# HVstuff.net
KiCad netlist of a schematic drawn in Altium Designer
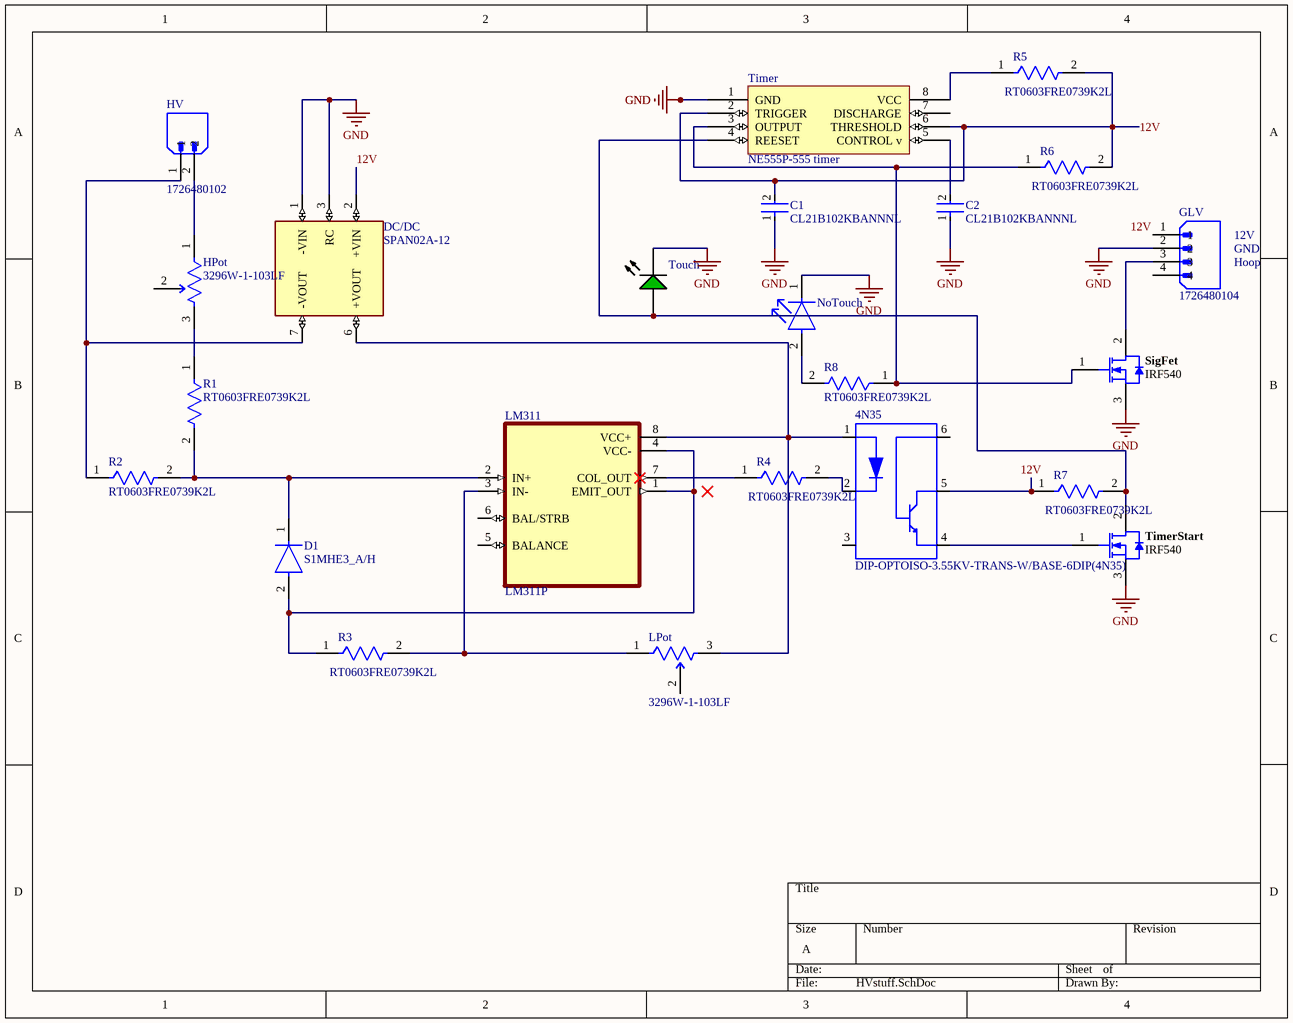
[diagram p0: HVstuff.SchDoc]

(export (version "E")
  (design (tool "Eeschema 10.0.6"))
  (components
    (comp (ref "4N35")
      (value "DIP-OPTOISO-3.55KV-TRANS-W/BASE-6DIP(4N35)")
      (footprint "DIP6-2.54-7.3X6.5MM")
      (description "Optoisolator Transistor with Base Output 5000Vrms 1 Channel 6-DIP")
      (fields (field (name "MF") "Vishay") (field (name "MP") "4N35"))
      (libsource (lib "DIP-OPTOISO-3.55KV-TRANS-W_BASE-6DIP_4N35_") (part "DIP-OPTOISO-3.55KV-TRANS-W/BASE-6DIP(4N35)"))
    )
    (comp (ref "C1")
      (value "CL21B102KBANNNL")
      (footprint "FP-CL21-IPC_A")
      (description "CL21 Series 0805 1nF 50V ±10% Tolerance X7R Multilayer Ceramic Chip Capacitor")
      (fields (field (name "TOLERANCE") "10%") (field (name "VOLTAGE") "50V"))
      (libsource (lib "Altium Content Vault") (part "b4654b650e69147ec39a6b967a45e02"))
    )
    (comp (ref "C2")
      (value "CL21B102KBANNNL")
      (footprint "FP-CL21-IPC_A")
      (description "CL21 Series 0805 1nF 50V ±10% Tolerance X7R Multilayer Ceramic Chip Capacitor")
      (fields (field (name "TOLERANCE") "10%") (field (name "VOLTAGE") "50V"))
      (libsource (lib "Altium Content Vault") (part "b4654b650e69147ec39a6b967a45e02"))
    )
    (comp (ref "D1")
      (value "S1MHE3_A/H")
      (footprint "FP-SMA-MFG")
      (description "DIODE GEN PURP 1KV 1A DO214AC")
      (libsource (lib "Altium Content Vault") (part "d7152d700b627762746794eb795d46e"))
    )
    (comp (ref "DC/DC")
      (value "SPAN02A-12")
      (footprint "SPAN02")
      (description "Isolated Module DC DC Converter 1 Output 12V - - - 167mA 9V - 18V Input")
      (fields (field (name "MF") "MEAN WELL USA Inc."))
      (libsource (lib "SPAN02A-12") (part "SPAN02A-12"))
    )
    (comp (ref "GLV")
      (value "1726480104")
      (footprint "MOLEX_1726480104")
      (description "Connector Header Through Hole, Right Angle 4 position 0.165in (4.20mm)")
      (libsource (lib "1726480104") (part "1726480104"))
    )
    (comp (ref "HPot")
      (value "3296W-1-103LF")
      (footprint "FP-3296W-MFG")
      (description "TRIMMER 10K OHM 0.5W PC PIN TOP")
      (fields (field (name "TOLERANCE") "10%"))
      (libsource (lib "Altium Content Vault") (part "2dcfd2547301a7d3209a5e99acfd772"))
    )
    (comp (ref "HV")
      (value "1726480102")
      (footprint "MOLEX_1726480102")
      (description "Connector Header Through Hole, Right Angle 2 position 0.165in (4.20mm)")
      (libsource (lib "1726480102") (part "1726480102"))
    )
    (comp (ref "LM311")
      (value "LM311P")
      (footprint "DIP794W45P254L959H508Q8")
      (description "High Speed, 30V, Differential Comparator With Strobes 8-PDIP 0 to 70")
      (fields (field (name "MF") "Texas Instruments"))
      (libsource (lib "LM311P") (part "LM311P"))
    )
    (comp (ref "LPot")
      (value "3296W-1-103LF")
      (footprint "FP-3296W-MFG")
      (description "TRIMMER 10K OHM 0.5W PC PIN TOP")
      (fields (field (name "TOLERANCE") "10%"))
      (libsource (lib "Altium Content Vault") (part "2dcfd2547301a7d3209a5e99acfd772"))
    )
    (comp (ref "NoTouch")
      (value "HSMS-C170")
      (footprint "FP-HSMS-C170-MFG")
      (description "LED RED DIFFUSED CHIP SMD")
      (libsource (lib "Altium Content Vault") (part "8706943c75ba83719d021d2fdc84c58"))
    )
    (comp (ref "R1")
      (value "RT0603FRE0739K2L")
      (footprint "FP-RT0603-MFG")
      (description "RES SMD 39.2K OHM 1% 1/10W 0603")
      (fields (field (name "MANUFACTURER") "Yageo") (field (name "TOLERANCE") "0.01"))
      (libsource (lib "Altium Content Vault") (part "1029c3af85768c4190bb7ad29bc67b5"))
    )
    (comp (ref "R2")
      (value "RT0603FRE0739K2L")
      (footprint "FP-RT0603-MFG")
      (description "RES SMD 39.2K OHM 1% 1/10W 0603")
      (fields (field (name "MANUFACTURER") "Yageo") (field (name "TOLERANCE") "0.01"))
      (libsource (lib "Altium Content Vault") (part "1029c3af85768c4190bb7ad29bc67b5"))
    )
    (comp (ref "R3")
      (value "RT0603FRE0739K2L")
      (footprint "FP-RT0603-MFG")
      (description "RES SMD 39.2K OHM 1% 1/10W 0603")
      (fields (field (name "MANUFACTURER") "Yageo") (field (name "TOLERANCE") "0.01"))
      (libsource (lib "Altium Content Vault") (part "1029c3af85768c4190bb7ad29bc67b5"))
    )
    (comp (ref "R4")
      (value "RT0603FRE0739K2L")
      (footprint "FP-RT0603-MFG")
      (description "RES SMD 39.2K OHM 1% 1/10W 0603")
      (fields (field (name "MANUFACTURER") "Yageo") (field (name "TOLERANCE") "0.01"))
      (libsource (lib "Altium Content Vault") (part "1029c3af85768c4190bb7ad29bc67b5"))
    )
    (comp (ref "R5")
      (value "RT0603FRE0739K2L")
      (footprint "FP-RT0603-MFG")
      (description "RES SMD 39.2K OHM 1% 1/10W 0603")
      (fields (field (name "MANUFACTURER") "Yageo") (field (name "TOLERANCE") "0.01"))
      (libsource (lib "Altium Content Vault") (part "1029c3af85768c4190bb7ad29bc67b5"))
    )
    (comp (ref "R6")
      (value "RT0603FRE0739K2L")
      (footprint "FP-RT0603-MFG")
      (description "RES SMD 39.2K OHM 1% 1/10W 0603")
      (fields (field (name "MANUFACTURER") "Yageo") (field (name "TOLERANCE") "0.01"))
      (libsource (lib "Altium Content Vault") (part "1029c3af85768c4190bb7ad29bc67b5"))
    )
    (comp (ref "R7")
      (value "RT0603FRE0739K2L")
      (footprint "FP-RT0603-MFG")
      (description "RES SMD 39.2K OHM 1% 1/10W 0603")
      (fields (field (name "MANUFACTURER") "Yageo") (field (name "TOLERANCE") "0.01"))
      (libsource (lib "Altium Content Vault") (part "1029c3af85768c4190bb7ad29bc67b5"))
    )
    (comp (ref "R8")
      (value "RT0603FRE0739K2L")
      (footprint "FP-RT0603-MFG")
      (description "RES SMD 39.2K OHM 1% 1/10W 0603")
      (fields (field (name "MANUFACTURER") "Yageo") (field (name "TOLERANCE") "0.01"))
      (libsource (lib "Altium Content Vault") (part "1029c3af85768c4190bb7ad29bc67b5"))
    )
    (comp (ref "SigFet")
      (value "IRF540")
      (footprint "VISH-TO-220AB-3_A")
      (description "Power MOSFET, 100 VDS, -55 to 175 degC, 3-Pin TO-220AB, RoHS, Tube")
      (fields (field (name "MANUFACTURER") "Vishay"))
      (libsource (lib "Altium Content Vault") (part "NEMOS-GDS-3"))
    )
    (comp (ref "Timer")
      (value "NE555P-555 timer")
      (footprint "NE555P-555 timer-Footprint-1")
      (description "555 timer")
      (libsource (lib "Luke Johnson") (part "NE555P-555 timer-Symbol-1"))
    )
    (comp (ref "TimerStart")
      (value "IRF540")
      (footprint "VISH-TO-220AB-3_A")
      (description "Power MOSFET, 100 VDS, -55 to 175 degC, 3-Pin TO-220AB, RoHS, Tube")
      (fields (field (name "MANUFACTURER") "Vishay"))
      (libsource (lib "Altium Content Vault") (part "NEMOS-GDS-3"))
    )
    (comp (ref "Touch")
      (value "HSMG-C170")
      (footprint "AVAG-HSMX-C170_V")
      (description "Chip LED, Green, 2.2 V, -40 to 85 degC, 2-Pin SMD, Pb-Free, Tape and Reel")
      (fields (field (name "MANUFACTURER") "Avago"))
      (libsource (lib "Altium Content Vault") (part "LED_GREEN_A1K2-2"))
    )
  )
  (nets
    (net (code "1") (name "/12V") (class "Default")
      (node (ref "4N35") (pin "5") (pinfunction "COLLECTOR_5") (pintype "bidirectional"))
      (node (ref "C1") (pin "2") (pinfunction "2_2") (pintype "passive"))
      (node (ref "DC/DC") (pin "2") (pinfunction "+VIN_2") (pintype "bidirectional"))
      (node (ref "GLV") (pin "1") (pinfunction "1_1") (pintype "passive"))
      (node (ref "R5") (pin "2") (pinfunction "2_2") (pintype "passive"))
      (node (ref "R6") (pin "2") (pinfunction "2_2") (pintype "passive"))
      (node (ref "R7") (pin "1") (pinfunction "1_1") (pintype "passive"))
      (node (ref "Timer") (pin "2") (pinfunction "TRIGGER_2") (pintype "bidirectional"))
      (node (ref "Timer") (pin "6") (pinfunction "THRESHOLD_6") (pintype "bidirectional"))
    )
    (net (code "2") (name "GND") (class "Default")
      (node (ref "C1") (pin "1") (pinfunction "1_1") (pintype "passive"))
      (node (ref "C2") (pin "1") (pinfunction "1_1") (pintype "passive"))
      (node (ref "DC/DC") (pin "1") (pinfunction "-VIN_1") (pintype "bidirectional"))
      (node (ref "DC/DC") (pin "3") (pinfunction "RC_3") (pintype "bidirectional"))
      (node (ref "GLV") (pin "2") (pinfunction "2_2") (pintype "passive"))
      (node (ref "NoTouch") (pin "1") (pinfunction "C_1") (pintype "passive"))
      (node (ref "SigFet") (pin "3") (pinfunction "S_3") (pintype "passive"))
      (node (ref "Timer") (pin "1") (pinfunction "GND_1") (pintype "power_in"))
      (node (ref "TimerStart") (pin "3") (pinfunction "S_3") (pintype "passive"))
      (node (ref "Touch") (pin "2") (pinfunction "K_2") (pintype "passive"))
    )
    (net (code "3") (name "Net-(4N35-ANODE)") (class "Default")
      (node (ref "4N35") (pin "1") (pinfunction "ANODE_1") (pintype "bidirectional"))
      (node (ref "DC/DC") (pin "6") (pinfunction "+VOUT_6") (pintype "bidirectional"))
      (node (ref "LM311") (pin "8") (pinfunction "VCC+_8") (pintype "power_in"))
      (node (ref "LPot") (pin "3") (pinfunction "CW_3") (pintype "passive"))
    )
    (net (code "4") (name "Net-(4N35-CATHODE)") (class "Default")
      (node (ref "4N35") (pin "2") (pinfunction "CATHODE_2") (pintype "bidirectional"))
      (node (ref "R4") (pin "2") (pinfunction "2_2") (pintype "passive"))
    )
    (net (code "5") (name "Net-(4N35-EMITER)") (class "Default")
      (node (ref "4N35") (pin "4") (pinfunction "EMITER_4") (pintype "bidirectional"))
      (node (ref "TimerStart") (pin "1") (pinfunction "G_1") (pintype "passive"))
    )
    (net (code "6") (name "Net-(D1-A)") (class "Default")
      (node (ref "D1") (pin "2") (pinfunction "A_2") (pintype "passive"))
      (node (ref "LM311") (pin "1") (pinfunction "EMIT_OUT_1") (pintype "output"))
      (node (ref "LM311") (pin "4") (pinfunction "VCC-_4") (pintype "power_in"))
      (node (ref "R3") (pin "1") (pinfunction "1_1") (pintype "passive"))
    )
    (net (code "7") (name "Net-(D1-C)") (class "Default")
      (node (ref "D1") (pin "1") (pinfunction "C_1") (pintype "passive"))
      (node (ref "LM311") (pin "2") (pinfunction "IN+_2") (pintype "input"))
      (node (ref "R1") (pin "2") (pinfunction "2_2") (pintype "passive"))
      (node (ref "R2") (pin "2") (pinfunction "2_2") (pintype "passive"))
    )
    (net (code "8") (name "Net-(DC/DC--VOUT)") (class "Default")
      (node (ref "DC/DC") (pin "7") (pinfunction "-VOUT_7") (pintype "bidirectional"))
      (node (ref "HV") (pin "1") (pinfunction "1_1") (pintype "passive"))
      (node (ref "R2") (pin "1") (pinfunction "1_1") (pintype "passive"))
    )
    (net (code "9") (name "Net-(HPot-CCW)") (class "Default")
      (node (ref "HPot") (pin "1") (pinfunction "CCW_1") (pintype "passive"))
      (node (ref "HV") (pin "2") (pinfunction "2_2") (pintype "passive"))
    )
    (net (code "10") (name "Net-(HPot-CW)") (class "Default")
      (node (ref "HPot") (pin "3") (pinfunction "CW_3") (pintype "passive"))
      (node (ref "R1") (pin "1") (pinfunction "1_1") (pintype "passive"))
    )
    (net (code "11") (name "Net-(LM311-COL_OUT)") (class "Default")
      (node (ref "LM311") (pin "7") (pinfunction "COL_OUT_7") (pintype "output"))
      (node (ref "R4") (pin "1") (pinfunction "1_1") (pintype "passive"))
    )
    (net (code "12") (name "Net-(LM311-IN-)") (class "Default")
      (node (ref "LM311") (pin "3") (pinfunction "IN-_3") (pintype "input"))
      (node (ref "LPot") (pin "1") (pinfunction "CCW_1") (pintype "passive"))
      (node (ref "R3") (pin "2") (pinfunction "2_2") (pintype "passive"))
    )
    (net (code "13") (name "Net-(NoTouch-A)") (class "Default")
      (node (ref "NoTouch") (pin "2") (pinfunction "A_2") (pintype "passive"))
      (node (ref "R8") (pin "2") (pinfunction "2_2") (pintype "passive"))
    )
    (net (code "14") (name "Net-(SigFet-D)") (class "Default")
      (node (ref "GLV") (pin "3") (pinfunction "3_3") (pintype "passive"))
      (node (ref "SigFet") (pin "2") (pinfunction "D_2") (pintype "passive"))
    )
    (net (code "15") (name "Net-(SigFet-G)") (class "Default")
      (node (ref "R6") (pin "1") (pinfunction "1_1") (pintype "passive"))
      (node (ref "R8") (pin "1") (pinfunction "1_1") (pintype "passive"))
      (node (ref "SigFet") (pin "1") (pinfunction "G_1") (pintype "passive"))
      (node (ref "Timer") (pin "3") (pinfunction "OUTPUT_3") (pintype "bidirectional"))
    )
    (net (code "16") (name "Net-(Timer-CONTROL_v)") (class "Default")
      (node (ref "C2") (pin "2") (pinfunction "2_2") (pintype "passive"))
      (node (ref "Timer") (pin "5") (pinfunction "CONTROL_v_5") (pintype "bidirectional"))
    )
    (net (code "17") (name "Net-(Timer-REESET)") (class "Default")
      (node (ref "R7") (pin "2") (pinfunction "2_2") (pintype "passive"))
      (node (ref "Timer") (pin "4") (pinfunction "REESET_4") (pintype "bidirectional"))
      (node (ref "TimerStart") (pin "2") (pinfunction "D_2") (pintype "passive"))
      (node (ref "Touch") (pin "1") (pinfunction "A_1") (pintype "passive"))
    )
    (net (code "18") (name "Net-(Timer-VCC)") (class "Default")
      (node (ref "R5") (pin "1") (pinfunction "1_1") (pintype "passive"))
      (node (ref "Timer") (pin "8") (pinfunction "VCC_8") (pintype "power_in"))
    )
    (net (code "19") (name "unconnected-(4N35-BASE-Pad6)") (class "Default")
      (node (ref "4N35") (pin "6") (pinfunction "BASE_6") (pintype "bidirectional"))
    )
    (net (code "20") (name "unconnected-(4N35-NC-Pad3)") (class "Default")
      (node (ref "4N35") (pin "3") (pinfunction "NC_3") (pintype "bidirectional"))
    )
    (net (code "21") (name "unconnected-(GLV-Pad4)") (class "Default")
      (node (ref "GLV") (pin "4") (pinfunction "4_4") (pintype "passive"))
    )
    (net (code "22") (name "unconnected-(HPot-WIPER-Pad2)") (class "Default")
      (node (ref "HPot") (pin "2") (pinfunction "WIPER_2") (pintype "passive"))
    )
    (net (code "23") (name "unconnected-(LM311-BALANCE-Pad5)") (class "Default")
      (node (ref "LM311") (pin "5") (pinfunction "BALANCE_5") (pintype "bidirectional"))
    )
    (net (code "24") (name "unconnected-(LM311-BAL{slash}STRB-Pad6)") (class "Default")
      (node (ref "LM311") (pin "6") (pinfunction "BAL/STRB_6") (pintype "bidirectional"))
    )
    (net (code "25") (name "unconnected-(LPot-WIPER-Pad2)") (class "Default")
      (node (ref "LPot") (pin "2") (pinfunction "WIPER_2") (pintype "passive"))
    )
    (net (code "26") (name "unconnected-(Timer-DISCHARGE-Pad7)") (class "Default")
      (node (ref "Timer") (pin "7") (pinfunction "DISCHARGE_7") (pintype "bidirectional"))
    )
  )
)
